# EVB-ANNA-B5_SCHEM_0002_ANNA_Module.net
KiCad netlist of a schematic drawn in Altium Designer
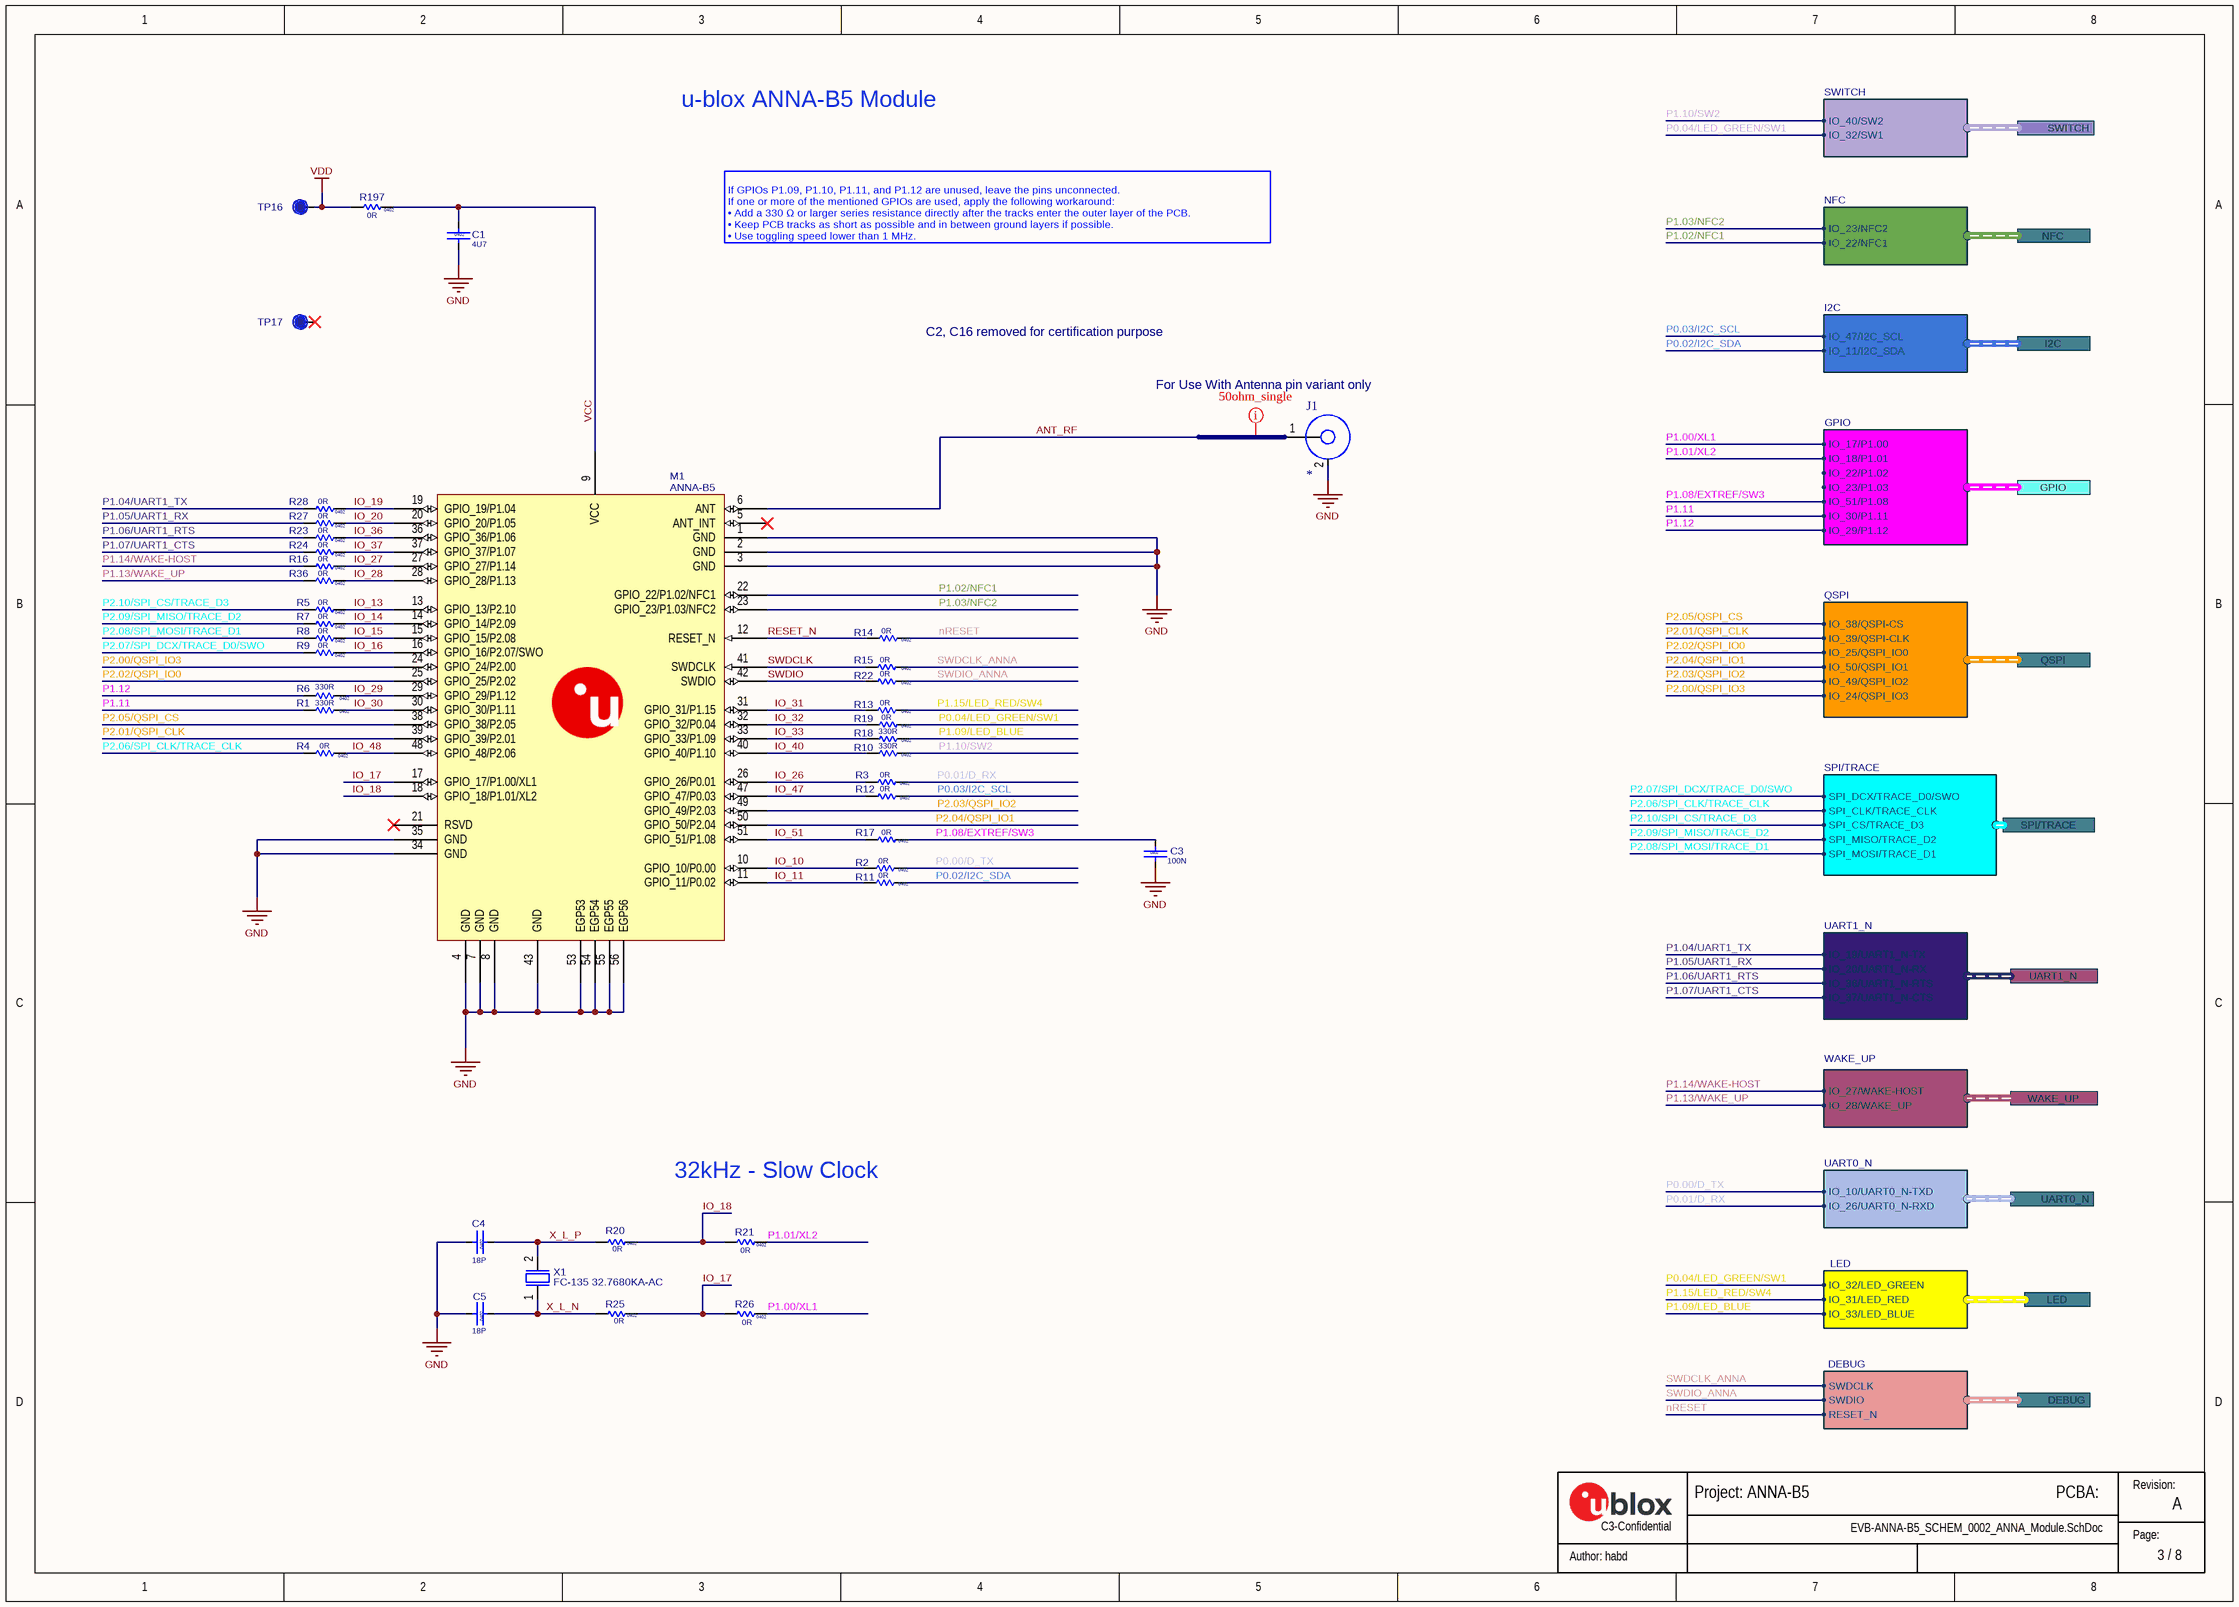
[diagram p0: EVB-ANNA-B5_SCHEM_0002_ANNA_Module.SchDoc]

(export (version "E")
  (design (tool "Eeschema 10.0.6"))
  (components
    (comp (ref "C1")
      (value "4U7")
      (footprint "Cap 0402 HD")
      (description "CAP CER X5R 0402 4U7 20% 10V")
      (fields
        (field (name "SIZE") "0402")
        (field (name "PART NUMBER") "UBXH01-0000243")
        (field (name "TOLERANCE") "20%")
        (field (name "EDITOR") "martin.pilik")
        (field (name "RELEASED BY") "fabrice.bret-dibat")
      )
      (libsource (lib "UBX_Parts_DB_Lib") (part "Cap Chip"))
    )
    (comp (ref "C3")
      (value "100N")
      (footprint "Cap 0402 HD")
      (description "CAP CER X5R 0402 100N 10% 10V")
      (fields
        (field (name "SIZE") "0402")
        (field (name "PART NUMBER") "UBXH01-2021002")
        (field (name "TOLERANCE") "10%")
        (field (name "EDITOR") "roland.rust")
        (field (name "RELEASED BY") "roland.rust")
      )
      (libsource (lib "UBX_Parts_DB_Lib") (part "Cap Chip"))
    )
    (comp (ref "C4")
      (value "18P")
      (footprint "Cap_0402_1100Lx600Wx600H_600x600Pad_350G_FLX")
      (description "CAP CER C0G 0402 18P 5% 25V")
      (fields
        (field (name "SIZE") "0402")
        (field (name "PART NUMBER") "UBXH01-0004017")
        (field (name "TOLERANCE") "5%")
        (field (name "EDITOR") "doris.zahnd")
        (field (name "RELEASED BY") "daniel.hurni")
      )
      (libsource (lib "UBX_Parts_DB_Lib") (part "Cap Chip"))
    )
    (comp (ref "C5")
      (value "18P")
      (footprint "Cap_0402_1100Lx600Wx600H_600x600Pad_350G_FLX")
      (description "CAP CER C0G 0402 18P 5% 25V")
      (fields
        (field (name "SIZE") "0402")
        (field (name "PART NUMBER") "UBXH01-0004017")
        (field (name "TOLERANCE") "5%")
        (field (name "EDITOR") "doris.zahnd")
        (field (name "RELEASED BY") "daniel.hurni")
      )
      (libsource (lib "UBX_Parts_DB_Lib") (part "Cap Chip"))
    )
    (comp (ref "J1")
      (value "130-00067")
      (footprint "U.FL_3Pin")
      (description "U.FL jack, SMA 50 ohm, 3 pin, SMT")
      (fields (field (name "MANUFACTURER P/N") "*") (field (name "VOLTAGE") "None"))
      (libsource (lib "Arena_Parts_DB_Lib") (part "CON_Coax_2Pin"))
    )
    (comp (ref "M1")
      (value "UBXH29-0000036")
      (footprint "ANNA-B5")
      (description "SHORT RANGE BLE AND IEEE802.15.4 SIP MODULE U-BLOX ANNA-B5")
      (fields
        (field (name "MANUFACTURER") "u-blox")
        (field (name "MANUFACTURER P/N") "ANNA-B5")
        (field (name "OWNER") "Yaqin Chen")
      )
      (libsource (lib "UBX_Arena") (part "ANNA-B5"))
    )
    (comp (ref "R1")
      (value "330R")
      (footprint "RES_0402_1100Lx600Wx400H_500x600Pad_400G_FLX")
      (description "RES THICK FILM CHIP 0402 330R 5% 63mW")
      (fields
        (field (name "SIZE") "0402")
        (field (name "PART NUMBER") "UBXH18-0008037")
        (field (name "TOLERANCE") "5%")
        (field (name "EDITOR") "daniel.hurni")
        (field (name "RELEASED BY") "doris.zahnd")
      )
      (libsource (lib "UBX_Parts_DB_Lib") (part "Res sm"))
    )
    (comp (ref "R2")
      (value "0R")
      (footprint "RES 0402 HD")
      (description "RES THICK FILM CHIP 0402 0R 0 100mW")
      (fields
        (field (name "SIZE") "0402")
        (field (name "PART NUMBER") "UBXH18-0003002")
        (field (name "TOLERANCE") "0")
        (field (name "EDITOR") "charlotte.biber")
        (field (name "RELEASED BY") "peter.mueller")
      )
      (libsource (lib "UBX_Parts_DB_Lib") (part "Res sm"))
    )
    (comp (ref "R3")
      (value "0R")
      (footprint "RES 0402 HD")
      (description "RES THICK FILM CHIP 0402 0R 0 100mW")
      (fields
        (field (name "SIZE") "0402")
        (field (name "PART NUMBER") "UBXH18-0003002")
        (field (name "TOLERANCE") "0")
        (field (name "EDITOR") "charlotte.biber")
        (field (name "RELEASED BY") "peter.mueller")
      )
      (libsource (lib "UBX_Parts_DB_Lib") (part "Res sm"))
    )
    (comp (ref "R4")
      (value "0R")
      (footprint "RES 0402 HD")
      (description "RES THICK FILM CHIP 0402 0R 0 100mW")
      (fields
        (field (name "SIZE") "0402")
        (field (name "PART NUMBER") "UBXH18-0003002")
        (field (name "TOLERANCE") "0")
        (field (name "EDITOR") "charlotte.biber")
        (field (name "RELEASED BY") "peter.mueller")
      )
      (libsource (lib "UBX_Parts_DB_Lib") (part "Res sm"))
    )
    (comp (ref "R5")
      (value "0R")
      (footprint "RES 0402 HD")
      (description "RES THICK FILM CHIP 0402 0R 0 100mW")
      (fields
        (field (name "SIZE") "0402")
        (field (name "PART NUMBER") "UBXH18-0003002")
        (field (name "TOLERANCE") "0")
        (field (name "EDITOR") "charlotte.biber")
        (field (name "RELEASED BY") "peter.mueller")
      )
      (libsource (lib "UBX_Parts_DB_Lib") (part "Res sm"))
    )
    (comp (ref "R6")
      (value "330R")
      (footprint "RES_0402_1100Lx600Wx400H_500x600Pad_400G_FLX")
      (description "RES THICK FILM CHIP 0402 330R 5% 63mW")
      (fields
        (field (name "SIZE") "0402")
        (field (name "PART NUMBER") "UBXH18-0008037")
        (field (name "TOLERANCE") "5%")
        (field (name "EDITOR") "daniel.hurni")
        (field (name "RELEASED BY") "doris.zahnd")
      )
      (libsource (lib "UBX_Parts_DB_Lib") (part "Res sm"))
    )
    (comp (ref "R7")
      (value "0R")
      (footprint "RES 0402 HD")
      (description "RES THICK FILM CHIP 0402 0R 0 100mW")
      (fields
        (field (name "SIZE") "0402")
        (field (name "PART NUMBER") "UBXH18-0003002")
        (field (name "TOLERANCE") "0")
        (field (name "EDITOR") "charlotte.biber")
        (field (name "RELEASED BY") "peter.mueller")
      )
      (libsource (lib "UBX_Parts_DB_Lib") (part "Res sm"))
    )
    (comp (ref "R8")
      (value "0R")
      (footprint "RES 0402 HD")
      (description "RES THICK FILM CHIP 0402 0R 0 100mW")
      (fields
        (field (name "SIZE") "0402")
        (field (name "PART NUMBER") "UBXH18-0003002")
        (field (name "TOLERANCE") "0")
        (field (name "EDITOR") "charlotte.biber")
        (field (name "RELEASED BY") "peter.mueller")
      )
      (libsource (lib "UBX_Parts_DB_Lib") (part "Res sm"))
    )
    (comp (ref "R9")
      (value "0R")
      (footprint "RES 0402 HD")
      (description "RES THICK FILM CHIP 0402 0R 0 100mW")
      (fields
        (field (name "SIZE") "0402")
        (field (name "PART NUMBER") "UBXH18-0003002")
        (field (name "TOLERANCE") "0")
        (field (name "EDITOR") "charlotte.biber")
        (field (name "RELEASED BY") "peter.mueller")
      )
      (libsource (lib "UBX_Parts_DB_Lib") (part "Res sm"))
    )
    (comp (ref "R10")
      (value "330R")
      (footprint "RES_0402_1100Lx600Wx400H_500x600Pad_400G_FLX")
      (description "RES THICK FILM CHIP 0402 330R 5% 63mW")
      (fields
        (field (name "SIZE") "0402")
        (field (name "PART NUMBER") "UBXH18-0008037")
        (field (name "TOLERANCE") "5%")
        (field (name "EDITOR") "daniel.hurni")
        (field (name "RELEASED BY") "doris.zahnd")
      )
      (libsource (lib "UBX_Parts_DB_Lib") (part "Res sm"))
    )
    (comp (ref "R11")
      (value "0R")
      (footprint "RES 0402 HD")
      (description "RES THICK FILM CHIP 0402 0R 0 100mW")
      (fields
        (field (name "SIZE") "0402")
        (field (name "PART NUMBER") "UBXH18-0003002")
        (field (name "TOLERANCE") "0")
        (field (name "EDITOR") "charlotte.biber")
        (field (name "RELEASED BY") "peter.mueller")
      )
      (libsource (lib "UBX_Parts_DB_Lib") (part "Res sm"))
    )
    (comp (ref "R12")
      (value "0R")
      (footprint "RES_0402_1100Lx600Wx400H_500x600Pad_400G_FLX")
      (description "RES THICK FILM CHIP 0402 0R 0 100mW")
      (fields
        (field (name "SIZE") "0402")
        (field (name "PART NUMBER") "UBXH18-0003002")
        (field (name "TOLERANCE") "0")
        (field (name "EDITOR") "charlotte.biber")
        (field (name "RELEASED BY") "peter.mueller")
      )
      (libsource (lib "UBX_Parts_DB_Lib") (part "Res sm"))
    )
    (comp (ref "R13")
      (value "0R")
      (footprint "RES_0402_1100Lx600Wx400H_500x600Pad_400G_FLX")
      (description "RES THICK FILM CHIP 0402 0R 0 100mW")
      (fields
        (field (name "SIZE") "0402")
        (field (name "PART NUMBER") "UBXH18-0003002")
        (field (name "TOLERANCE") "0")
        (field (name "EDITOR") "charlotte.biber")
        (field (name "RELEASED BY") "peter.mueller")
      )
      (libsource (lib "UBX_Parts_DB_Lib") (part "Res sm"))
    )
    (comp (ref "R14")
      (value "0R")
      (footprint "RES_0402_1100Lx600Wx400H_500x600Pad_400G_FLX")
      (description "RES THICK FILM CHIP 0402 0R 0 100mW")
      (fields
        (field (name "SIZE") "0402")
        (field (name "PART NUMBER") "UBXH18-0003002")
        (field (name "TOLERANCE") "0")
        (field (name "EDITOR") "charlotte.biber")
        (field (name "RELEASED BY") "peter.mueller")
      )
      (libsource (lib "UBX_Parts_DB_Lib") (part "Res sm"))
    )
    (comp (ref "R15")
      (value "0R")
      (footprint "RES 0402 HD")
      (description "RES THICK FILM CHIP 0402 0R 0 100mW")
      (fields
        (field (name "SIZE") "0402")
        (field (name "PART NUMBER") "UBXH18-0003002")
        (field (name "TOLERANCE") "0")
        (field (name "EDITOR") "charlotte.biber")
        (field (name "RELEASED BY") "peter.mueller")
      )
      (libsource (lib "UBX_Parts_DB_Lib") (part "Res sm"))
    )
    (comp (ref "R16")
      (value "0R")
      (footprint "RES 0402 HD")
      (description "RES THICK FILM CHIP 0402 0R 0 100mW")
      (fields
        (field (name "SIZE") "0402")
        (field (name "PART NUMBER") "UBXH18-0003002")
        (field (name "TOLERANCE") "0")
        (field (name "EDITOR") "charlotte.biber")
        (field (name "RELEASED BY") "peter.mueller")
      )
      (libsource (lib "UBX_Parts_DB_Lib") (part "Res sm"))
    )
    (comp (ref "R17")
      (value "0R")
      (footprint "RES 0402 HD")
      (description "RES THICK FILM CHIP 0402 0R 0 100mW")
      (fields
        (field (name "SIZE") "0402")
        (field (name "PART NUMBER") "UBXH18-0003002")
        (field (name "TOLERANCE") "0")
        (field (name "EDITOR") "charlotte.biber")
        (field (name "RELEASED BY") "peter.mueller")
      )
      (libsource (lib "UBX_Parts_DB_Lib") (part "Res sm"))
    )
    (comp (ref "R18")
      (value "330R")
      (footprint "RES_0402_1100Lx600Wx400H_500x600Pad_400G_FLX")
      (description "RES THICK FILM CHIP 0402 330R 5% 63mW")
      (fields
        (field (name "SIZE") "0402")
        (field (name "PART NUMBER") "UBXH18-0008037")
        (field (name "TOLERANCE") "5%")
        (field (name "EDITOR") "daniel.hurni")
        (field (name "RELEASED BY") "doris.zahnd")
      )
      (libsource (lib "UBX_Parts_DB_Lib") (part "Res sm"))
    )
    (comp (ref "R19")
      (value "0R")
      (footprint "RES 0402 HD")
      (description "RES THICK FILM CHIP 0402 0R 0 100mW")
      (fields
        (field (name "SIZE") "0402")
        (field (name "PART NUMBER") "UBXH18-0003002")
        (field (name "TOLERANCE") "0")
        (field (name "EDITOR") "charlotte.biber")
        (field (name "RELEASED BY") "peter.mueller")
      )
      (libsource (lib "UBX_Parts_DB_Lib") (part "Res sm"))
    )
    (comp (ref "R20")
      (value "0R")
      (footprint "RES 0402 HD")
      (description "RES THICK FILM CHIP 0402 0R 0 100mW")
      (fields
        (field (name "SIZE") "0402")
        (field (name "PART NUMBER") "UBXH18-0003002")
        (field (name "TOLERANCE") "0")
        (field (name "EDITOR") "charlotte.biber")
        (field (name "RELEASED BY") "peter.mueller")
      )
      (libsource (lib "UBX_Parts_DB_Lib") (part "Res sm"))
    )
    (comp (ref "R21")
      (value "0R")
      (footprint "RES_0402_1100Lx600Wx400H_500x600Pad_400G_FLX")
      (description "RES THICK FILM CHIP 0402 0R 0 100mW")
      (fields
        (field (name "SIZE") "0402")
        (field (name "PART NUMBER") "UBXH18-0003002")
        (field (name "TOLERANCE") "0")
        (field (name "EDITOR") "charlotte.biber")
        (field (name "RELEASED BY") "peter.mueller")
      )
      (libsource (lib "UBX_Parts_DB_Lib") (part "Res sm"))
    )
    (comp (ref "R22")
      (value "0R")
      (footprint "RES 0402 HD")
      (description "RES THICK FILM CHIP 0402 0R 0 100mW")
      (fields
        (field (name "SIZE") "0402")
        (field (name "PART NUMBER") "UBXH18-0003002")
        (field (name "TOLERANCE") "0")
        (field (name "EDITOR") "charlotte.biber")
        (field (name "RELEASED BY") "peter.mueller")
      )
      (libsource (lib "UBX_Parts_DB_Lib") (part "Res sm"))
    )
    (comp (ref "R23")
      (value "0R")
      (footprint "RES 0402 HD")
      (description "RES THICK FILM CHIP 0402 0R 0 100mW")
      (fields
        (field (name "SIZE") "0402")
        (field (name "PART NUMBER") "UBXH18-0003002")
        (field (name "TOLERANCE") "0")
        (field (name "EDITOR") "charlotte.biber")
        (field (name "RELEASED BY") "peter.mueller")
      )
      (libsource (lib "UBX_Parts_DB_Lib") (part "Res sm"))
    )
    (comp (ref "R24")
      (value "0R")
      (footprint "RES 0402 HD")
      (description "RES THICK FILM CHIP 0402 0R 0 100mW")
      (fields
        (field (name "SIZE") "0402")
        (field (name "PART NUMBER") "UBXH18-0003002")
        (field (name "TOLERANCE") "0")
        (field (name "EDITOR") "charlotte.biber")
        (field (name "RELEASED BY") "peter.mueller")
      )
      (libsource (lib "UBX_Parts_DB_Lib") (part "Res sm"))
    )
    (comp (ref "R25")
      (value "0R")
      (footprint "RES 0402 HD")
      (description "RES THICK FILM CHIP 0402 0R 0 100mW")
      (fields
        (field (name "SIZE") "0402")
        (field (name "PART NUMBER") "UBXH18-0003002")
        (field (name "TOLERANCE") "0")
        (field (name "EDITOR") "charlotte.biber")
        (field (name "RELEASED BY") "peter.mueller")
      )
      (libsource (lib "UBX_Parts_DB_Lib") (part "Res sm"))
    )
    (comp (ref "R26")
      (value "0R")
      (footprint "RES_0402_1100Lx600Wx400H_500x600Pad_400G_FLX")
      (description "RES THICK FILM CHIP 0402 0R 0 100mW")
      (fields
        (field (name "SIZE") "0402")
        (field (name "PART NUMBER") "UBXH18-0003002")
        (field (name "TOLERANCE") "0")
        (field (name "EDITOR") "charlotte.biber")
        (field (name "RELEASED BY") "peter.mueller")
      )
      (libsource (lib "UBX_Parts_DB_Lib") (part "Res sm"))
    )
    (comp (ref "R27")
      (value "0R")
      (footprint "RES 0402 HD")
      (description "RES THICK FILM CHIP 0402 0R 0 100mW")
      (fields
        (field (name "SIZE") "0402")
        (field (name "PART NUMBER") "UBXH18-0003002")
        (field (name "TOLERANCE") "0")
        (field (name "EDITOR") "charlotte.biber")
        (field (name "RELEASED BY") "peter.mueller")
      )
      (libsource (lib "UBX_Parts_DB_Lib") (part "Res sm"))
    )
    (comp (ref "R28")
      (value "0R")
      (footprint "RES 0402 HD")
      (description "RES THICK FILM CHIP 0402 0R 0 100mW")
      (fields
        (field (name "SIZE") "0402")
        (field (name "PART NUMBER") "UBXH18-0003002")
        (field (name "TOLERANCE") "0")
        (field (name "EDITOR") "charlotte.biber")
        (field (name "RELEASED BY") "peter.mueller")
      )
      (libsource (lib "UBX_Parts_DB_Lib") (part "Res sm"))
    )
    (comp (ref "R36")
      (value "0R")
      (footprint "RES_0402_1100Lx600Wx400H_500x600Pad_400G_FLX")
      (description "RES THICK FILM CHIP 0402 0R 0 100mW")
      (fields
        (field (name "SIZE") "0402")
        (field (name "PART NUMBER") "UBXH18-0003002")
        (field (name "TOLERANCE") "0")
        (field (name "EDITOR") "charlotte.biber")
        (field (name "RELEASED BY") "peter.mueller")
      )
      (libsource (lib "UBX_Parts_DB_Lib") (part "Res sm"))
    )
    (comp (ref "R197")
      (value "0R")
      (footprint "RES 0402 HD")
      (description "RES THICK FILM CHIP 0402 0R 0 100mW")
      (fields
        (field (name "SIZE") "0402")
        (field (name "PART NUMBER") "UBXH18-0003002")
        (field (name "TOLERANCE") "0")
        (field (name "EDITOR") "charlotte.biber")
        (field (name "RELEASED BY") "peter.mueller")
      )
      (libsource (lib "UBX_Parts_DB_Lib") (part "Res sm"))
    )
    (comp (ref "TP16")
      (value "TP10R")
      (footprint "TP10R")
      (description "Testpoint, Round 1.0mm Dia")
      (fields (field (name "ADDED BY") "Jeremy D") (field (name "CHECKED BY") "Paul B"))
      (libsource (lib "LEGACY_Rigado_AltiumLib") (part "TP_R"))
    )
    (comp (ref "TP17")
      (value "TP10R")
      (footprint "TP10R")
      (description "Testpoint, Round 1.0mm Dia")
      (fields (field (name "ADDED BY") "Jeremy D") (field (name "CHECKED BY") "Paul B"))
      (libsource (lib "LEGACY_Rigado_AltiumLib") (part "TP_R"))
    )
    (comp (ref "X1")
      (value "UBXH21-0008104")
      (footprint "XTAL_3215")
      (description "CRYSTAL CL=9PF EPSON FC-135 NI/SN TERMINATION 32.768KHz")
      (fields (field (name "MANUFACTURER P/N") "FC-135 32.7680KA-AC") (field (name "OWNER") "Andreas Thiel"))
      (libsource (lib "UBX_Arena") (part "XTAL_2Pin"))
    )
  )
  (nets
    (net (code "12") (name "/ANT_RF") (class "Default")
      (node (ref "J1") (pin "1") (pinfunction "ANT_1") (pintype "passive"))
      (node (ref "M1") (pin "6") (pinfunction "ANT_6") (pintype "bidirectional"))
    )
    (net (code "13") (name "/IO_10") (class "Default")
      (node (ref "M1") (pin "10") (pinfunction "GPIO_10/P0.00_10") (pintype "bidirectional"))
      (node (ref "R2") (pin "2") (pinfunction "2_2") (pintype "passive"))
    )
    (net (code "14") (name "/IO_11") (class "Default")
      (node (ref "M1") (pin "11") (pinfunction "GPIO_11/P0.02_11") (pintype "bidirectional"))
      (node (ref "R11") (pin "1") (pinfunction "1_1") (pintype "passive"))
    )
    (net (code "15") (name "/IO_13") (class "Default")
      (node (ref "M1") (pin "13") (pinfunction "GPIO_13/P2.10_13") (pintype "bidirectional"))
      (node (ref "R5") (pin "2") (pinfunction "2_2") (pintype "passive"))
    )
    (net (code "16") (name "/IO_14") (class "Default")
      (node (ref "M1") (pin "14") (pinfunction "GPIO_14/P2.09_14") (pintype "bidirectional"))
      (node (ref "R7") (pin "2") (pinfunction "2_2") (pintype "passive"))
    )
    (net (code "17") (name "/IO_15") (class "Default")
      (node (ref "M1") (pin "15") (pinfunction "GPIO_15/P2.08_15") (pintype "bidirectional"))
      (node (ref "R8") (pin "2") (pinfunction "2_2") (pintype "passive"))
    )
    (net (code "18") (name "/IO_16") (class "Default")
      (node (ref "M1") (pin "16") (pinfunction "GPIO_16/P2.07/SWO_16") (pintype "bidirectional"))
      (node (ref "R9") (pin "2") (pinfunction "2_2") (pintype "passive"))
    )
    (net (code "19") (name "/IO_17") (class "Default")
      (node (ref "M1") (pin "17") (pinfunction "GPIO_17/P1.00/XL1_17") (pintype "bidirectional"))
      (node (ref "R25") (pin "2") (pinfunction "2_2") (pintype "passive"))
      (node (ref "R26") (pin "2") (pinfunction "2_2") (pintype "passive"))
    )
    (net (code "20") (name "/IO_18") (class "Default")
      (node (ref "M1") (pin "18") (pinfunction "GPIO_18/P1.01/XL2_18") (pintype "bidirectional"))
      (node (ref "R20") (pin "2") (pinfunction "2_2") (pintype "passive"))
      (node (ref "R21") (pin "2") (pinfunction "2_2") (pintype "passive"))
    )
    (net (code "21") (name "/IO_19") (class "Default")
      (node (ref "M1") (pin "19") (pinfunction "GPIO_19/P1.04_19") (pintype "bidirectional"))
      (node (ref "R28") (pin "1") (pinfunction "1_1") (pintype "passive"))
    )
    (net (code "22") (name "/IO_20") (class "Default")
      (node (ref "M1") (pin "20") (pinfunction "GPIO_20/P1.05_20") (pintype "bidirectional"))
      (node (ref "R27") (pin "1") (pinfunction "1_1") (pintype "passive"))
    )
    (net (code "23") (name "/IO_26") (class "Default")
      (node (ref "M1") (pin "26") (pinfunction "GPIO_26/P0.01_26") (pintype "bidirectional"))
      (node (ref "R3") (pin "2") (pinfunction "2_2") (pintype "passive"))
    )
    (net (code "24") (name "/IO_27") (class "Default")
      (node (ref "M1") (pin "27") (pinfunction "GPIO_27/P1.14_27") (pintype "bidirectional"))
      (node (ref "R16") (pin "2") (pinfunction "2_2") (pintype "passive"))
    )
    (net (code "25") (name "/IO_28") (class "Default")
      (node (ref "M1") (pin "28") (pinfunction "GPIO_28/P1.13_28") (pintype "bidirectional"))
      (node (ref "R36") (pin "1") (pinfunction "1_1") (pintype "passive"))
    )
    (net (code "26") (name "/IO_29") (class "Default")
      (node (ref "M1") (pin "29") (pinfunction "GPIO_29/P1.12_29") (pintype "bidirectional"))
      (node (ref "R6") (pin "2") (pinfunction "2_2") (pintype "passive"))
    )
    (net (code "27") (name "/IO_30") (class "Default")
      (node (ref "M1") (pin "30") (pinfunction "GPIO_30/P1.11_30") (pintype "bidirectional"))
      (node (ref "R1") (pin "2") (pinfunction "2_2") (pintype "passive"))
    )
    (net (code "28") (name "/IO_31") (class "Default")
      (node (ref "M1") (pin "31") (pinfunction "GPIO_31/P1.15_31") (pintype "bidirectional"))
      (node (ref "R13") (pin "1") (pinfunction "1_1") (pintype "passive"))
    )
    (net (code "29") (name "/IO_32") (class "Default")
      (node (ref "M1") (pin "32") (pinfunction "GPIO_32/P0.04_32") (pintype "bidirectional"))
      (node (ref "R19") (pin "1") (pinfunction "1_1") (pintype "passive"))
    )
    (net (code "30") (name "/IO_33") (class "Default")
      (node (ref "M1") (pin "33") (pinfunction "GPIO_33/P1.09_33") (pintype "bidirectional"))
      (node (ref "R18") (pin "2") (pinfunction "2_2") (pintype "passive"))
    )
    (net (code "31") (name "/IO_36") (class "Default")
      (node (ref "M1") (pin "36") (pinfunction "GPIO_36/P1.06_36") (pintype "bidirectional"))
      (node (ref "R23") (pin "2") (pinfunction "2_2") (pintype "passive"))
    )
    (net (code "32") (name "/IO_37") (class "Default")
      (node (ref "M1") (pin "37") (pinfunction "GPIO_37/P1.07_37") (pintype "bidirectional"))
      (node (ref "R24") (pin "2") (pinfunction "2_2") (pintype "passive"))
    )
    (net (code "33") (name "/IO_40") (class "Default")
      (node (ref "M1") (pin "40") (pinfunction "GPIO_40/P1.10_40") (pintype "bidirectional"))
      (node (ref "R10") (pin "2") (pinfunction "2_2") (pintype "passive"))
    )
    (net (code "34") (name "/IO_47") (class "Default")
      (node (ref "M1") (pin "47") (pinfunction "GPIO_47/P0.03_47") (pintype "bidirectional"))
      (node (ref "R12") (pin "1") (pinfunction "1_1") (pintype "passive"))
    )
    (net (code "35") (name "/IO_48") (class "Default")
      (node (ref "M1") (pin "48") (pinfunction "GPIO_48/P2.06_48") (pintype "bidirectional"))
      (node (ref "R4") (pin "2") (pinfunction "2_2") (pintype "passive"))
    )
    (net (code "36") (name "/IO_51") (class "Default")
      (node (ref "M1") (pin "51") (pinfunction "GPIO_51/P1.08_51") (pintype "bidirectional"))
      (node (ref "R17") (pin "2") (pinfunction "2_2") (pintype "passive"))
    )
    (net (code "37") (name "/P0.00{slash}D_TX") (class "Default")
      (node (ref "R2") (pin "1") (pinfunction "1_1") (pintype "passive"))
    )
    (net (code "38") (name "/P0.01{slash}D_RX") (class "Default")
      (node (ref "R3") (pin "1") (pinfunction "1_1") (pintype "passive"))
    )
    (net (code "39") (name "/P0.02{slash}I2C_SDA") (class "Default")
      (node (ref "R11") (pin "2") (pinfunction "2_2") (pintype "passive"))
    )
    (net (code "40") (name "/P0.03{slash}I2C_SCL") (class "Default")
      (node (ref "R12") (pin "2") (pinfunction "2_2") (pintype "passive"))
    )
    (net (code "41") (name "/P0.04{slash}LED_GREEN{slash}SW1") (class "Default")
      (node (ref "R19") (pin "2") (pinfunction "2_2") (pintype "passive"))
    )
    (net (code "42") (name "/P1.00{slash}XL1") (class "Default")
      (node (ref "R26") (pin "1") (pinfunction "1_1") (pintype "passive"))
    )
    (net (code "43") (name "/P1.01{slash}XL2") (class "Default")
      (node (ref "R21") (pin "1") (pinfunction "1_1") (pintype "passive"))
    )
    (net (code "44") (name "/P1.02{slash}NFC1") (class "Default")
      (node (ref "M1") (pin "22") (pinfunction "GPIO_22/P1.02/NFC1_22") (pintype "bidirectional"))
    )
    (net (code "45") (name "/P1.03{slash}NFC2") (class "Default")
      (node (ref "M1") (pin "23") (pinfunction "GPIO_23/P1.03/NFC2_23") (pintype "bidirectional"))
    )
    (net (code "46") (name "/P1.04{slash}UART1_TX") (class "Default")
      (node (ref "R28") (pin "2") (pinfunction "2_2") (pintype "passive"))
    )
    (net (code "47") (name "/P1.05{slash}UART1_RX") (class "Default")
      (node (ref "R27") (pin "2") (pinfunction "2_2") (pintype "passive"))
    )
    (net (code "48") (name "/P1.06{slash}UART1_RTS") (class "Default")
      (node (ref "R23") (pin "1") (pinfunction "1_1") (pintype "passive"))
    )
    (net (code "49") (name "/P1.07{slash}UART1_CTS") (class "Default")
      (node (ref "R24") (pin "1") (pinfunction "1_1") (pintype "passive"))
    )
    (net (code "50") (name "/P1.08{slash}EXTREF{slash}SW3") (class "Default")
      (node (ref "C3") (pin "2") (pinfunction "2_2") (pintype "passive"))
      (node (ref "R17") (pin "1") (pinfunction "1_1") (pintype "passive"))
    )
    (net (code "51") (name "/P1.09{slash}LED_BLUE") (class "Default")
      (node (ref "R18") (pin "1") (pinfunction "1_1") (pintype "passive"))
    )
    (net (code "52") (name "/P1.10{slash}SW2") (class "Default")
      (node (ref "R10") (pin "1") (pinfunction "1_1") (pintype "passive"))
    )
    (net (code "53") (name "/P1.11") (class "Default")
      (node (ref "R1") (pin "1") (pinfunction "1_1") (pintype "passive"))
    )
    (net (code "54") (name "/P1.12") (class "Default")
      (node (ref "R6") (pin "1") (pinfunction "1_1") (pintype "passive"))
    )
    (net (code "55") (name "/P1.13{slash}WAKE_UP") (class "Default")
      (node (ref "R36") (pin "2") (pinfunction "2_2") (pintype "passive"))
    )
    (net (code "56") (name "/P1.14{slash}WAKE-HOST") (class "Default")
      (node (ref "R16") (pin "1") (pinfunction "1_1") (pintype "passive"))
    )
    (net (code "57") (name "/P1.15{slash}LED_RED{slash}SW4") (class "Default")
      (node (ref "R13") (pin "2") (pinfunction "2_2") (pintype "passive"))
    )
    (net (code "58") (name "/P2.00{slash}QSPI_IO3") (class "Default")
      (node (ref "M1") (pin "24") (pinfunction "GPIO_24/P2.00_24") (pintype "bidirectional"))
    )
    (net (code "59") (name "/P2.01{slash}QSPI_CLK") (class "Default")
      (node (ref "M1") (pin "39") (pinfunction "GPIO_39/P2.01_39") (pintype "bidirectional"))
    )
    (net (code "60") (name "/P2.02{slash}QSPI_IO0") (class "Default")
      (node (ref "M1") (pin "25") (pinfunction "GPIO_25/P2.02_25") (pintype "bidirectional"))
    )
    (net (code "61") (name "/P2.03{slash}QSPI_IO2") (class "Default")
      (node (ref "M1") (pin "49") (pinfunction "GPIO_49/P2.03_49") (pintype "bidirectional"))
    )
    (net (code "62") (name "/P2.04{slash}QSPI_IO1") (class "Default")
      (node (ref "M1") (pin "50") (pinfunction "GPIO_50/P2.04_50") (pintype "bidirectional"))
    )
    (net (code "63") (name "/P2.05{slash}QSPI_CS") (class "Default")
      (node (ref "M1") (pin "38") (pinfunction "GPIO_38/P2.05_38") (pintype "bidirectional"))
    )
    (net (code "64") (name "/P2.06{slash}SPI_CLK{slash}TRACE_CLK") (class "Default")
      (node (ref "R4") (pin "1") (pinfunction "1_1") (pintype "passive"))
    )
    (net (code "65") (name "/P2.07{slash}SPI_DCX{slash}TRACE_D0{slash}SWO") (class "Default")
      (node (ref "R9") (pin "1") (pinfunction "1_1") (pintype "passive"))
    )
    (net (code "66") (name "/P2.08{slash}SPI_MOSI{slash}TRACE_D1") (class "Default")
      (node (ref "R8") (pin "1") (pinfunction "1_1") (pintype "passive"))
    )
    (net (code "67") (name "/P2.09{slash}SPI_MISO{slash}TRACE_D2") (class "Default")
      (node (ref "R7") (pin "1") (pinfunction "1_1") (pintype "passive"))
    )
    (net (code "68") (name "/P2.10{slash}SPI_CS{slash}TRACE_D3") (class "Default")
      (node (ref "R5") (pin "1") (pinfunction "1_1") (pintype "passive"))
    )
    (net (code "69") (name "/RESET_N") (class "Default")
      (node (ref "M1") (pin "12") (pinfunction "RESET_N_12") (pintype "input"))
      (node (ref "R14") (pin "1") (pinfunction "1_1") (pintype "passive"))
    )
    (net (code "70") (name "/SWDCLK") (class "Default")
      (node (ref "M1") (pin "41") (pinfunction "SWDCLK_41") (pintype "input"))
      (node (ref "R15") (pin "1") (pinfunction "1_1") (pintype "passive"))
    )
    (net (code "71") (name "/SWDCLK_ANNA") (class "Default")
      (node (ref "R15") (pin "2") (pinfunction "2_2") (pintype "passive"))
    )
    (net (code "72") (name "/SWDIO") (class "Default")
      (node (ref "M1") (pin "42") (pinfunction "SWDIO_42") (pintype "bidirectional"))
      (node (ref "R22") (pin "1") (pinfunction "1_1") (pintype "passive"))
    )
    (net (code "73") (name "/SWDIO_ANNA") (class "Default")
      (node (ref "R22") (pin "2") (pinfunction "2_2") (pintype "passive"))
    )
    (net (code "74") (name "/VCC") (class "Default")
      (node (ref "C1") (pin "1") (pinfunction "1_1") (pintype "passive"))
      (node (ref "M1") (pin "9") (pinfunction "VCC_9") (pintype "power_in"))
      (node (ref "R197") (pin "1") (pinfunction "1_1") (pintype "passive"))
    )
    (net (code "75") (name "/X_L_N") (class "Default")
      (node (ref "C5") (pin "1") (pinfunction "1_1") (pintype "passive"))
      (node (ref "R25") (pin "1") (pinfunction "1_1") (pintype "passive"))
      (node (ref "X1") (pin "1") (pintype "passive"))
    )
    (net (code "76") (name "/X_L_P") (class "Default")
      (node (ref "C4") (pin "1") (pinfunction "1_1") (pintype "passive"))
      (node (ref "R20") (pin "1") (pinfunction "1_1") (pintype "passive"))
      (node (ref "X1") (pin "2") (pintype "passive"))
    )
    (net (code "77") (name "/nRESET") (class "Default")
      (node (ref "R14") (pin "2") (pinfunction "2_2") (pintype "passive"))
    )
    (net (code "89") (name "GND") (class "Default")
      (node (ref "C1") (pin "2") (pinfunction "2_2") (pintype "passive"))
      (node (ref "C3") (pin "1") (pinfunction "1_1") (pintype "passive"))
      (node (ref "C4") (pin "2") (pinfunction "2_2") (pintype "passive"))
      (node (ref "C5") (pin "2") (pinfunction "2_2") (pintype "passive"))
      (node (ref "J1") (pin "2") (pinfunction "2_2") (pintype "power_in"))
      (node (ref "M1") (pin "1") (pinfunction "GND_1") (pintype "power_in"))
      (node (ref "M1") (pin "2") (pinfunction "GND_2") (pintype "power_in"))
      (node (ref "M1") (pin "3") (pinfunction "GND_3") (pintype "power_in"))
      (node (ref "M1") (pin "34") (pinfunction "GND_34") (pintype "power_in"))
      (node (ref "M1") (pin "35") (pinfunction "GND_35") (pintype "power_in"))
      (node (ref "M1") (pin "4") (pinfunction "GND_4") (pintype "power_in"))
      (node (ref "M1") (pin "43") (pinfunction "GND_43") (pintype "power_in"))
      (node (ref "M1") (pin "53") (pinfunction "EGP53_53") (pintype "power_in"))
      (node (ref "M1") (pin "54") (pinfunction "EGP54_54") (pintype "power_in"))
      (node (ref "M1") (pin "55") (pinfunction "EGP55_55") (pintype "power_in"))
      (node (ref "M1") (pin "56") (pinfunction "EGP56_56") (pintype "power_in"))
      (node (ref "M1") (pin "7") (pinfunction "GND_7") (pintype "power_in"))
      (node (ref "M1") (pin "8") (pinfunction "GND_8") (pintype "power_in"))
    )
    (net (code "90") (name "VDD") (class "Default")
      (node (ref "R197") (pin "2") (pinfunction "2_2") (pintype "passive"))
      (node (ref "TP16") (pin "1") (pintype "passive"))
    )
    (net (code "91") (name "unconnected-(M1-ANT_INT-Pad5)") (class "Default")
      (node (ref "M1") (pin "5") (pinfunction "ANT_INT_5") (pintype "bidirectional+no_connect"))
    )
    (net (code "92") (name "unconnected-(M1-RSVD-Pad21)") (class "Default")
      (node (ref "M1") (pin "21") (pinfunction "RSVD_21") (pintype "power_in+no_connect"))
    )
    (net (code "93") (name "unconnected-(TP17-Pad1)") (class "Default")
      (node (ref "TP17") (pin "1") (pintype "passive+no_connect"))
    )
  )
)
